# 04_ADC.net
KiCad netlist of a schematic drawn in Altium Designer
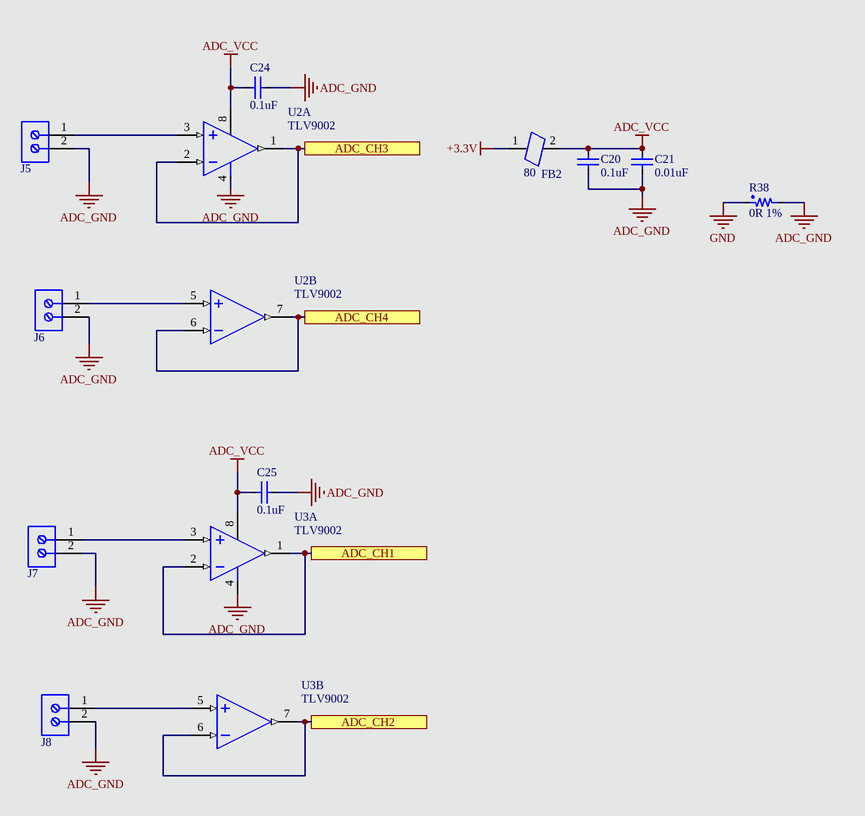
[diagram p0: 04_ADC.SchDoc]

(export (version "E")
  (design (tool "Eeschema 10.0.6"))
  (components
    (comp (ref "C20")
      (value "0.1uF")
      (footprint "Capacitor:C0603 (1608 metric)")
      (description "Multilayer Ceramic Capacitors MLCC - SMD/SMT 0.1uF 50V X7R +/-10% 0603")
      (fields (field (name "MFR PART NUMBER") "CC0603KRX7R9BB104") (field (name "MFR") "Yageo"))
      (libsource (lib "CeramicCapacitor") (part "CC0603KRX7R9BB104"))
    )
    (comp (ref "C21")
      (value "0.01uF")
      (footprint "Capacitor:C0603 (1608 metric)")
      (description "Multilayer Ceramic Capacitors MLCC - SMD/SMT 0.01uF 50V X7R +/-10% 0603")
      (fields (field (name "MFR PART NUMBER") "CC0603KRX7R9BB103") (field (name "MFR") "Yageo"))
      (libsource (lib "CeramicCapacitor") (part "CC0603KRX7R9BB103"))
    )
    (comp (ref "C24")
      (value "0.1uF")
      (footprint "Capacitor:C0603 (1608 metric)")
      (description "Multilayer Ceramic Capacitors MLCC - SMD/SMT 0.1uF 50V X7R +/-10% 0603")
      (fields (field (name "MFR PART NUMBER") "CC0603KRX7R9BB104") (field (name "MFR") "Yageo"))
      (libsource (lib "CeramicCapacitor") (part "CC0603KRX7R9BB104"))
    )
    (comp (ref "C25")
      (value "0.1uF")
      (footprint "Capacitor:C0603 (1608 metric)")
      (description "Multilayer Ceramic Capacitors MLCC - SMD/SMT 0.1uF 50V X7R +/-10% 0603")
      (fields (field (name "MFR PART NUMBER") "CC0603KRX7R9BB104") (field (name "MFR") "Yageo"))
      (libsource (lib "CeramicCapacitor") (part "CC0603KRX7R9BB104"))
    )
    (comp (ref "FB2")
      (value "80")
      (footprint "Inductor:FB0805 (2012 METRIC)")
      (description "Ferrite Beads HI CUR CHIP BD 0805 80OHMS 25%")
      (fields (field (name "MFR PART NUMBER") "FBMH2012HM800-T") (field (name "MFR") "Taiyo Yuden"))
      (libsource (lib "FerriteBead") (part "FBMH2012HM800-T"))
    )
    (comp (ref "J5")
      (value "691103110002")
      (footprint "691103110002")
      (description "WR-TBL Series 1031 Horizontal Entry Modular, THT, pitch 3.5mm, 2p")
      (fields (field (name "MFR") "Wurth Elektronik"))
      (libsource (lib "Altium_WR-TBL (rev22b)") (part "691103110002"))
    )
    (comp (ref "J6")
      (value "691103110002")
      (footprint "691103110002")
      (description "WR-TBL Series 1031 Horizontal Entry Modular, THT, pitch 3.5mm, 2p")
      (fields (field (name "MFR") "Wurth Elektronik"))
      (libsource (lib "Altium_WR-TBL (rev22b)") (part "691103110002"))
    )
    (comp (ref "J7")
      (value "691103110002")
      (footprint "691103110002")
      (description "WR-TBL Series 1031 Horizontal Entry Modular, THT, pitch 3.5mm, 2p")
      (fields (field (name "MFR") "Wurth Elektronik"))
      (libsource (lib "Altium_WR-TBL (rev22b)") (part "691103110002"))
    )
    (comp (ref "J8")
      (value "691103110002")
      (footprint "691103110002")
      (description "WR-TBL Series 1031 Horizontal Entry Modular, THT, pitch 3.5mm, 2p")
      (fields (field (name "MFR") "Wurth Elektronik"))
      (libsource (lib "Altium_WR-TBL (rev22b)") (part "691103110002"))
    )
    (comp (ref "R38")
      (value "0R 1%")
      (footprint "Resistor:R0603 (1608 Metric)")
      (description "Thick Film Resistors - SMD 0 OHM 1% Case 0603")
      (fields (field (name "MFR PART NUMBER") "RC0603FR-070RL") (field (name "MFR") "Yageo"))
      (libsource (lib "ChipResistor") (part "RC0603FR-070RL"))
    )
    (comp (ref "U2")
      (value "TLV9002")
      (footprint "IC:VSSOP-8_DGK")
      (description "General Purpose Amplifier 2 Circuit Rail-to-Rail 8-VSSOP")
      (fields (field (name "MFR") "Texas Instruments") (field (name "MFR PART NUMBER") "TLV9002IDGKR"))
      (libsource (lib "Opamp") (part "TLV9002IDGKR"))
    )
    (comp (ref "U3")
      (value "TLV9002")
      (footprint "IC:VSSOP-8_DGK")
      (description "General Purpose Amplifier 2 Circuit Rail-to-Rail 8-VSSOP")
      (fields (field (name "MFR") "Texas Instruments") (field (name "MFR PART NUMBER") "TLV9002IDGKR"))
      (libsource (lib "Opamp") (part "TLV9002IDGKR"))
    )
  )
  (nets
    (net (code "1") (name "+3.3V") (class "Default")
      (node (ref "FB2") (pin "1") (pinfunction "1_1") (pintype "passive"))
    )
    (net (code "2") (name "/ADC_CH1") (class "Default")
      (node (ref "U3") (pin "1") (pinfunction "OUT_1") (pintype "output"))
      (node (ref "U3") (pin "2") (pinfunction "IN-_2") (pintype "input"))
    )
    (net (code "3") (name "/ADC_CH2") (class "Default")
      (node (ref "U3") (pin "6") (pinfunction "IN-_6") (pintype "input"))
      (node (ref "U3") (pin "7") (pinfunction "OUT_7") (pintype "output"))
    )
    (net (code "4") (name "/ADC_CH3") (class "Default")
      (node (ref "U2") (pin "1") (pinfunction "OUT_1") (pintype "output"))
      (node (ref "U2") (pin "2") (pinfunction "IN-_2") (pintype "input"))
    )
    (net (code "5") (name "/ADC_CH4") (class "Default")
      (node (ref "U2") (pin "6") (pinfunction "IN-_6") (pintype "input"))
      (node (ref "U2") (pin "7") (pinfunction "OUT_7") (pintype "output"))
    )
    (net (code "6") (name "ADC_GND") (class "Default")
      (node (ref "C20") (pin "1") (pinfunction "1_1") (pintype "passive"))
      (node (ref "C21") (pin "1") (pinfunction "1_1") (pintype "passive"))
      (node (ref "C24") (pin "2") (pinfunction "2_2") (pintype "passive"))
      (node (ref "C25") (pin "2") (pinfunction "2_2") (pintype "passive"))
      (node (ref "J5") (pin "2") (pinfunction "2_2") (pintype "passive"))
      (node (ref "J6") (pin "2") (pinfunction "2_2") (pintype "passive"))
      (node (ref "J7") (pin "2") (pinfunction "2_2") (pintype "passive"))
      (node (ref "J8") (pin "2") (pinfunction "2_2") (pintype "passive"))
      (node (ref "R38") (pin "2") (pinfunction "2_2") (pintype "passive"))
      (node (ref "U2") (pin "4") (pinfunction "-V_4") (pintype "passive"))
      (node (ref "U3") (pin "4") (pinfunction "-V_4") (pintype "passive"))
    )
    (net (code "7") (name "ADC_VCC") (class "Default")
      (node (ref "C20") (pin "2") (pinfunction "2_2") (pintype "passive"))
      (node (ref "C21") (pin "2") (pinfunction "2_2") (pintype "passive"))
      (node (ref "C24") (pin "1") (pinfunction "1_1") (pintype "passive"))
      (node (ref "C25") (pin "1") (pinfunction "1_1") (pintype "passive"))
      (node (ref "FB2") (pin "2") (pinfunction "2_2") (pintype "passive"))
      (node (ref "U2") (pin "8") (pinfunction "+V_8") (pintype "passive"))
      (node (ref "U3") (pin "8") (pinfunction "+V_8") (pintype "passive"))
    )
    (net (code "8") (name "GND") (class "Default")
      (node (ref "R38") (pin "1") (pinfunction "1_1") (pintype "passive"))
    )
    (net (code "9") (name "Net-(U2A-IN+)") (class "Default")
      (node (ref "J5") (pin "1") (pinfunction "1_1") (pintype "passive"))
      (node (ref "U2") (pin "3") (pinfunction "IN+_3") (pintype "input"))
    )
    (net (code "10") (name "Net-(U2B-IN+)") (class "Default")
      (node (ref "J6") (pin "1") (pinfunction "1_1") (pintype "passive"))
      (node (ref "U2") (pin "5") (pinfunction "IN+_5") (pintype "input"))
    )
    (net (code "11") (name "Net-(U3A-IN+)") (class "Default")
      (node (ref "J7") (pin "1") (pinfunction "1_1") (pintype "passive"))
      (node (ref "U3") (pin "3") (pinfunction "IN+_3") (pintype "input"))
    )
    (net (code "12") (name "Net-(U3B-IN+)") (class "Default")
      (node (ref "J8") (pin "1") (pinfunction "1_1") (pintype "passive"))
      (node (ref "U3") (pin "5") (pinfunction "IN+_5") (pintype "input"))
    )
  )
)
